# BM78SPP05NC2.net
KiCad netlist of a schematic drawn in Altium Designer
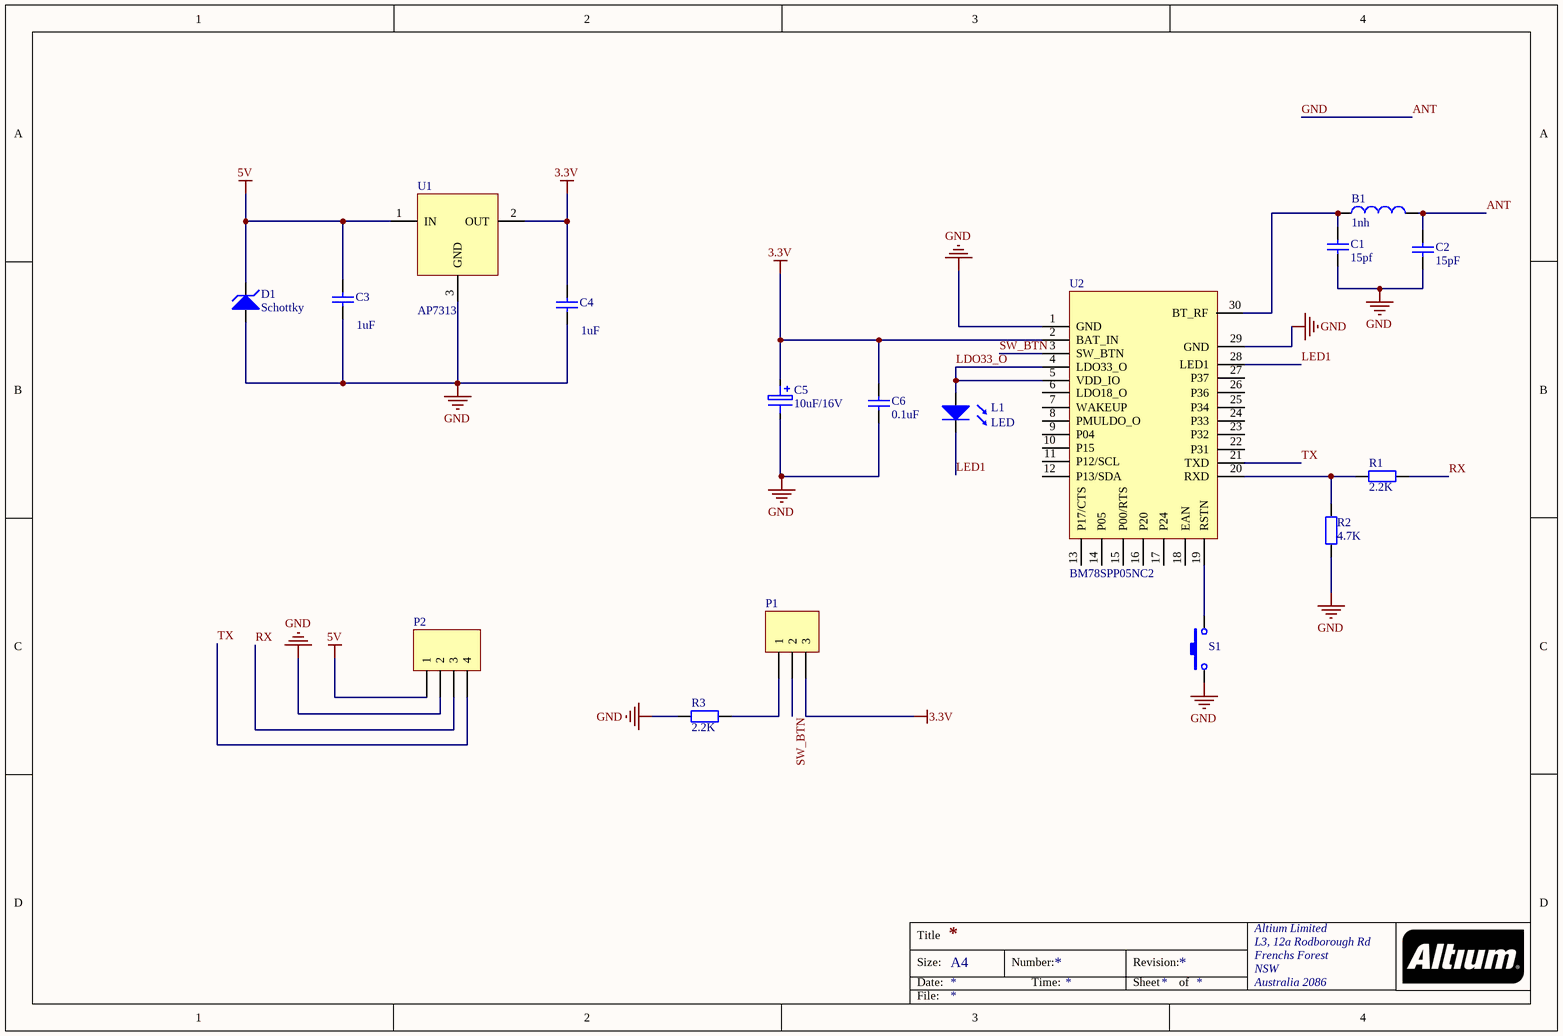
[diagram p0: BM78SPP05NC2.SchDoc]

(export (version "E")
  (design (tool "Eeschema 10.0.6"))
  (components
    (comp (ref "B1") (value "1nh") (footprint "0603") (libsource (lib "ToponLib") (part "Bead")))
    (comp (ref "C1")
      (value "15pf")
      (footprint "0603")
      (description "ceramic")
      (libsource (lib "ToponLib") (part "Cap1"))
    )
    (comp (ref "C2")
      (value "15pF")
      (footprint "0603")
      (description "ceramic")
      (libsource (lib "ToponLib") (part "Cap1"))
    )
    (comp (ref "C3")
      (value "1uF")
      (footprint "0603")
      (description "ceramic")
      (libsource (lib "ToponLib") (part "Cap1"))
    )
    (comp (ref "C4")
      (value "1uF")
      (footprint "0603")
      (description "ceramic")
      (libsource (lib "ToponLib") (part "Cap1"))
    )
    (comp (ref "C5")
      (value "10uF/16V")
      (footprint "1206")
      (description "aluminum")
      (libsource (lib "ToponLib") (part "Cap3"))
    )
    (comp (ref "C6")
      (value "0.1uF")
      (footprint "0603")
      (description "ceramic")
      (libsource (lib "ToponLib") (part "Cap1"))
    )
    (comp (ref "D1")
      (value "Schottky")
      (footprint "DO214-AC")
      (libsource (lib "ToponLib") (part "B340A-13-F"))
    )
    (comp (ref "L1") (value "LED") (footprint "0805") (libsource (lib "ToponLib") (part "LED")))
    (comp (ref "P1")
      (value "HC-SR501")
      (footprint "Header3")
      (description "Header, 3-Pin")
      (fields (field (name "PUBLISHER") "Altium Limited"))
      (libsource (lib "ToponLib") (part "Header 3"))
    )
    (comp (ref "P2")
      (value "Header 4")
      (footprint "HDR1X4")
      (description "Header, 4-Pin")
      (fields (field (name "PUBLISHER") "Altium Limited"))
      (libsource (lib "Miscellaneous Connectors") (part "Header 4"))
    )
    (comp (ref "R1") (value "2.2K") (footprint "0603") (libsource (lib "") (part "Res_1")))
    (comp (ref "R2") (value "4.7K") (footprint "0603") (libsource (lib "ToponLib") (part "Res")))
    (comp (ref "R3") (value "2.2K") (footprint "0603") (libsource (lib "") (part "Res_2")))
    (comp (ref "S1") (value "Button") (footprint "BUtton-T4") (libsource (lib "ToponLib") (part "Button")))
    (comp (ref "U1")
      (value "AP7313")
      (footprint "AP7313-33SAG-7")
      (libsource (lib "ToponLib") (part "AP7313-33SAG-7"))
    )
    (comp (ref "U2")
      (value "BM78SPP05NC2")
      (footprint "BM78SPP05NC2")
      (libsource (lib "ToponLib") (part "BM78SPP05NC2"))
    )
  )
  (nets
    (net (code "1") (name "/LDO33_O") (class "Default")
      (node (ref "L1") (pin "1") (pinfunction "A_1") (pintype "passive"))
      (node (ref "U2") (pin "4") (pinfunction "LDO33_O_4") (pintype "passive"))
      (node (ref "U2") (pin "5") (pinfunction "VDD_IO_5") (pintype "passive"))
    )
    (net (code "2") (name "/LED1") (class "Default")
      (node (ref "L1") (pin "2") (pinfunction "K_2") (pintype "passive"))
      (node (ref "U2") (pin "28") (pinfunction "LED1_28") (pintype "passive"))
    )
    (net (code "3") (name "/RX") (class "Default")
      (node (ref "P2") (pin "3") (pinfunction "3_3") (pintype "passive"))
      (node (ref "R1") (pin "1") (pinfunction "1_1") (pintype "passive"))
    )
    (net (code "4") (name "/SW_BTN") (class "Default")
      (node (ref "P1") (pin "2") (pinfunction "2_2") (pintype "passive"))
      (node (ref "U2") (pin "3") (pinfunction "SW_BTN_3") (pintype "passive"))
    )
    (net (code "5") (name "/TX") (class "Default")
      (node (ref "P2") (pin "4") (pinfunction "4_4") (pintype "passive"))
      (node (ref "U2") (pin "21") (pinfunction "TXD_21") (pintype "passive"))
    )
    (net (code "6") (name "3.3V") (class "Default")
      (node (ref "C4") (pin "2") (pinfunction "2_2") (pintype "passive"))
      (node (ref "C5") (pin "1") (pinfunction "1_1") (pintype "passive"))
      (node (ref "C6") (pin "1") (pinfunction "1_1") (pintype "passive"))
      (node (ref "P1") (pin "3") (pinfunction "3_3") (pintype "passive"))
      (node (ref "U1") (pin "2") (pinfunction "OUT_2") (pintype "passive"))
      (node (ref "U2") (pin "2") (pinfunction "BAT_IN_2") (pintype "passive"))
    )
    (net (code "7") (name "5V") (class "Default")
      (node (ref "C3") (pin "2") (pinfunction "2_2") (pintype "passive"))
      (node (ref "D1") (pin "2") (pinfunction "K_2") (pintype "passive"))
      (node (ref "P2") (pin "1") (pinfunction "1_1") (pintype "passive"))
      (node (ref "U1") (pin "1") (pinfunction "IN_1") (pintype "passive"))
    )
    (net (code "8") (name "GND") (class "Default")
      (node (ref "B1") (pin "2") (pinfunction "2_2") (pintype "passive"))
      (node (ref "C1") (pin "1") (pinfunction "1_1") (pintype "passive"))
      (node (ref "C2") (pin "1") (pinfunction "1_1") (pintype "passive"))
      (node (ref "C2") (pin "2") (pinfunction "2_2") (pintype "passive"))
      (node (ref "C3") (pin "1") (pinfunction "1_1") (pintype "passive"))
      (node (ref "C4") (pin "1") (pinfunction "1_1") (pintype "passive"))
      (node (ref "C5") (pin "2") (pinfunction "2_2") (pintype "passive"))
      (node (ref "C6") (pin "2") (pinfunction "2_2") (pintype "passive"))
      (node (ref "D1") (pin "1") (pinfunction "A_1") (pintype "passive"))
      (node (ref "P2") (pin "2") (pinfunction "2_2") (pintype "passive"))
      (node (ref "R2") (pin "1") (pinfunction "1_1") (pintype "passive"))
      (node (ref "R3") (pin "1") (pinfunction "1_1") (pintype "passive"))
      (node (ref "S1") (pin "1") (pinfunction "1_1") (pintype "passive"))
      (node (ref "U1") (pin "3") (pinfunction "GND_3") (pintype "passive"))
      (node (ref "U2") (pin "1") (pinfunction "GND_1") (pintype "passive"))
      (node (ref "U2") (pin "29") (pinfunction "GND_29") (pintype "passive"))
    )
    (net (code "9") (name "Net-(P1-Pad1)") (class "Default")
      (node (ref "P1") (pin "1") (pinfunction "1_1") (pintype "passive"))
      (node (ref "R3") (pin "2") (pinfunction "2_2") (pintype "passive"))
    )
    (net (code "10") (name "Net-(U2-BT_RF)") (class "Default")
      (node (ref "B1") (pin "1") (pinfunction "1_1") (pintype "passive"))
      (node (ref "C1") (pin "2") (pinfunction "2_2") (pintype "passive"))
      (node (ref "U2") (pin "30") (pinfunction "BT_RF_30") (pintype "passive"))
    )
    (net (code "11") (name "Net-(U2-RSTN)") (class "Default")
      (node (ref "S1") (pin "2") (pinfunction "2_2") (pintype "passive"))
      (node (ref "U2") (pin "19") (pinfunction "RSTN_19") (pintype "passive"))
    )
    (net (code "12") (name "Net-(U2-RXD)") (class "Default")
      (node (ref "R1") (pin "2") (pinfunction "2_2") (pintype "passive"))
      (node (ref "R2") (pin "2") (pinfunction "2_2") (pintype "passive"))
      (node (ref "U2") (pin "20") (pinfunction "RXD_20") (pintype "passive"))
    )
    (net (code "13") (name "unconnected-(U2-EAN-Pad18)") (class "Default")
      (node (ref "U2") (pin "18") (pinfunction "EAN_18") (pintype "passive"))
    )
    (net (code "14") (name "unconnected-(U2-LDO18_O-Pad6)") (class "Default")
      (node (ref "U2") (pin "6") (pinfunction "LDO18_O_6") (pintype "passive"))
    )
    (net (code "15") (name "unconnected-(U2-P00{slash}RTS-Pad15)") (class "Default")
      (node (ref "U2") (pin "15") (pinfunction "P00/RTS_15") (pintype "passive"))
    )
    (net (code "16") (name "unconnected-(U2-P04-Pad9)") (class "Default")
      (node (ref "U2") (pin "9") (pinfunction "P04_9") (pintype "passive"))
    )
    (net (code "17") (name "unconnected-(U2-P05-Pad14)") (class "Default")
      (node (ref "U2") (pin "14") (pinfunction "P05_14") (pintype "passive"))
    )
    (net (code "18") (name "unconnected-(U2-P12{slash}SCL-Pad11)") (class "Default")
      (node (ref "U2") (pin "11") (pinfunction "P12/SCL_11") (pintype "passive"))
    )
    (net (code "19") (name "unconnected-(U2-P13{slash}SDA-Pad12)") (class "Default")
      (node (ref "U2") (pin "12") (pinfunction "P13/SDA_12") (pintype "passive"))
    )
    (net (code "20") (name "unconnected-(U2-P15-Pad10)") (class "Default")
      (node (ref "U2") (pin "10") (pinfunction "P15_10") (pintype "passive"))
    )
    (net (code "21") (name "unconnected-(U2-P17{slash}CTS-Pad13)") (class "Default")
      (node (ref "U2") (pin "13") (pinfunction "P17/CTS_13") (pintype "passive"))
    )
    (net (code "22") (name "unconnected-(U2-P20-Pad16)") (class "Default")
      (node (ref "U2") (pin "16") (pinfunction "P20_16") (pintype "passive"))
    )
    (net (code "23") (name "unconnected-(U2-P24-Pad17)") (class "Default")
      (node (ref "U2") (pin "17") (pinfunction "P24_17") (pintype "passive"))
    )
    (net (code "24") (name "unconnected-(U2-P31-Pad22)") (class "Default")
      (node (ref "U2") (pin "22") (pinfunction "P31_22") (pintype "passive"))
    )
    (net (code "25") (name "unconnected-(U2-P32-Pad23)") (class "Default")
      (node (ref "U2") (pin "23") (pinfunction "P32_23") (pintype "passive"))
    )
    (net (code "26") (name "unconnected-(U2-P33-Pad24)") (class "Default")
      (node (ref "U2") (pin "24") (pinfunction "P33_24") (pintype "passive"))
    )
    (net (code "27") (name "unconnected-(U2-P34-Pad25)") (class "Default")
      (node (ref "U2") (pin "25") (pinfunction "P34_25") (pintype "passive"))
    )
    (net (code "28") (name "unconnected-(U2-P36-Pad26)") (class "Default")
      (node (ref "U2") (pin "26") (pinfunction "P36_26") (pintype "passive"))
    )
    (net (code "29") (name "unconnected-(U2-P37-Pad27)") (class "Default")
      (node (ref "U2") (pin "27") (pinfunction "P37_27") (pintype "passive"))
    )
    (net (code "30") (name "unconnected-(U2-PMULDO_O-Pad8)") (class "Default")
      (node (ref "U2") (pin "8") (pinfunction "PMULDO_O_8") (pintype "passive"))
    )
    (net (code "31") (name "unconnected-(U2-WAKEUP-Pad7)") (class "Default")
      (node (ref "U2") (pin "7") (pinfunction "WAKEUP_7") (pintype "passive"))
    )
  )
)
